# uC_radio.net
KiCad netlist of a schematic drawn in Altium Designer
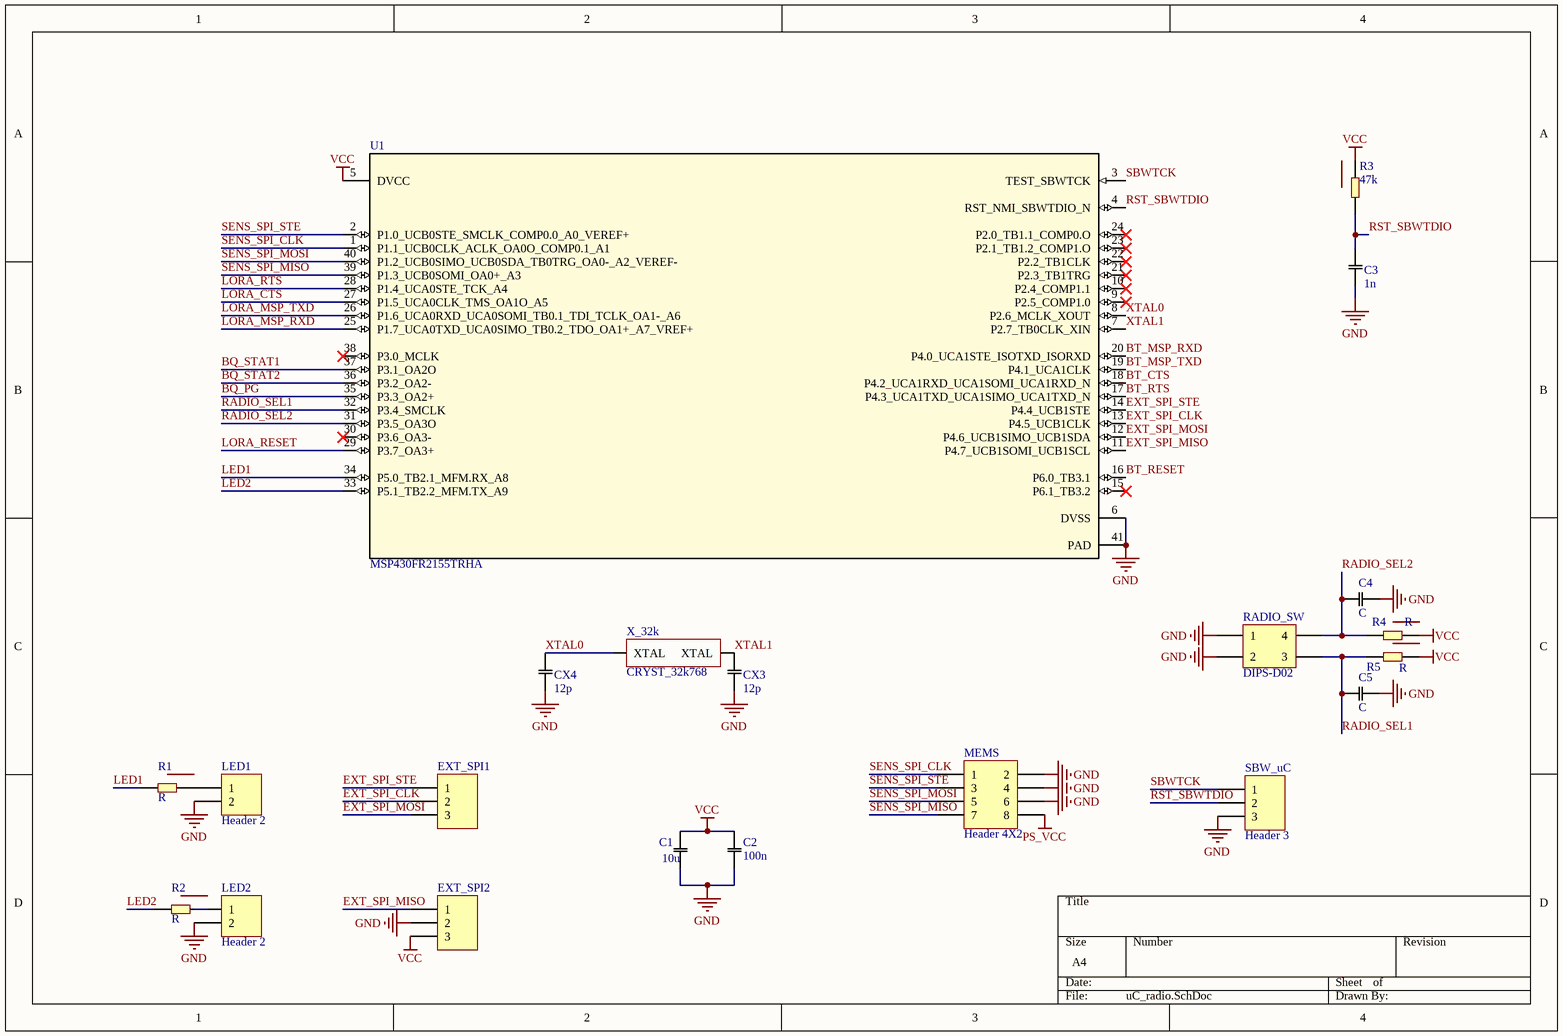
[diagram p0: uC_radio.SchDoc]

(export (version "E")
  (design (tool "Eeschema 10.0.6"))
  (components
    (comp (ref "C1")
      (value "10u")
      (footprint "402")
      (description "Capacitor")
      (libsource (lib "pass_comp") (part "C"))
    )
    (comp (ref "C2")
      (value "100n")
      (footprint "402")
      (description "Capacitor")
      (libsource (lib "pass_comp") (part "C"))
    )
    (comp (ref "C3")
      (value "1n")
      (footprint "402")
      (description "Capacitor")
      (libsource (lib "pass_comp") (part "C"))
    )
    (comp (ref "C4")
      (value "C")
      (footprint "603")
      (description "Capacitor")
      (libsource (lib "pass_comp") (part "C"))
    )
    (comp (ref "C5")
      (value "C")
      (footprint "603")
      (description "Capacitor")
      (libsource (lib "pass_comp") (part "C"))
    )
    (comp (ref "CX3")
      (value "12p")
      (footprint "402")
      (description "Capacitor")
      (libsource (lib "pass_comp") (part "C"))
    )
    (comp (ref "CX4")
      (value "12p")
      (footprint "402")
      (description "Capacitor")
      (libsource (lib "pass_comp") (part "C"))
    )
    (comp (ref "EXT_SPI1")
      (value "~")
      (footprint "HDR1X3")
      (description "Header, 3-Pin")
      (fields (field (name "PUBLISHER") "Altium Limited"))
      (libsource (lib "Miscellaneous Connectors") (part "Header 3"))
    )
    (comp (ref "EXT_SPI2")
      (value "~")
      (footprint "HDR1X3")
      (description "Header, 3-Pin")
      (fields (field (name "PUBLISHER") "Altium Limited"))
      (libsource (lib "Miscellaneous Connectors") (part "Header 3"))
    )
    (comp (ref "LED1")
      (value "Header 2")
      (footprint "HDR1X2")
      (description "Header, 2-Pin")
      (fields (field (name "PUBLISHER") "Altium Limited"))
      (libsource (lib "Miscellaneous Connectors") (part "Header 2"))
    )
    (comp (ref "LED2")
      (value "Header 2")
      (footprint "HDR1X2")
      (description "Header, 2-Pin")
      (fields (field (name "PUBLISHER") "Altium Limited"))
      (libsource (lib "Miscellaneous Connectors") (part "Header 2"))
    )
    (comp (ref "MEMS")
      (value "Header 4X2")
      (footprint "HDR2X4")
      (description "Header, 4-Pin, Dual row")
      (fields (field (name "PUBLISHER") "Altium Limited"))
      (libsource (lib "Miscellaneous Connectors") (part "Header 4X2"))
    )
    (comp (ref "R1") (value "R") (footprint "402") (description "Resistor") (libsource (lib "") (part "R_1")))
    (comp (ref "R2") (value "R") (footprint "402") (description "Resistor") (libsource (lib "") (part "R_1")))
    (comp (ref "R3")
      (value "47k")
      (footprint "402")
      (description "Resistor")
      (libsource (lib "pass_comp") (part "R"))
    )
    (comp (ref "R4") (value "R") (footprint "402") (description "Resistor") (libsource (lib "") (part "R_1")))
    (comp (ref "R5") (value "R") (footprint "402") (description "Resistor") (libsource (lib "") (part "R_1")))
    (comp (ref "RADIO_SW")
      (value "DIPS-D02")
      (footprint "DIPS-02")
      (libsource (lib "env_sens") (part "DIPS-D02"))
    )
    (comp (ref "SBW_uC")
      (value "Header 3")
      (footprint "HDR1X3")
      (description "Header, 3-Pin")
      (fields (field (name "PUBLISHER") "Altium Limited"))
      (libsource (lib "Miscellaneous Connectors") (part "Header 3"))
    )
    (comp (ref "U1")
      (value "MSP430FR2155TRHA")
      (footprint "RHA0040E_NV")
      (description "Imported")
      (fields
        (field (name "MANUFACTURER") "Texas Instruments")
        (field (name "PARTNUMBER") "MSP430FR2355TRHAR")
      )
      (libsource (lib "env_sens") (part "MSP430FR2155TRHA"))
    )
    (comp (ref "X_32k")
      (value "CRYST_32k768")
      (footprint "CRYST 32.768 kHz")
      (libsource (lib "env_sens") (part "CRYST_32k768"))
    )
  )
  (nets
    (net (code "1") (name "/BQ_PG") (class "Default")
      (node (ref "U1") (pin "35") (pinfunction "P3.3_OA2+_35") (pintype "bidirectional"))
    )
    (net (code "2") (name "/BQ_STAT1") (class "Default")
      (node (ref "U1") (pin "37") (pinfunction "P3.1_OA2O_37") (pintype "bidirectional"))
    )
    (net (code "3") (name "/BQ_STAT2") (class "Default")
      (node (ref "U1") (pin "36") (pinfunction "P3.2_OA2-_36") (pintype "bidirectional"))
    )
    (net (code "4") (name "/BT_CTS") (class "Default")
      (node (ref "U1") (pin "18") (pinfunction "P4.2_UCA1RXD_UCA1SOMI_UCA1RXD_N_18") (pintype "bidirectional"))
    )
    (net (code "5") (name "/BT_MSP_RXD") (class "Default")
      (node (ref "U1") (pin "20") (pinfunction "P4.0_UCA1STE_ISOTXD_ISORXD_20") (pintype "bidirectional"))
    )
    (net (code "6") (name "/BT_MSP_TXD") (class "Default")
      (node (ref "U1") (pin "19") (pinfunction "P4.1_UCA1CLK_19") (pintype "bidirectional"))
    )
    (net (code "7") (name "/BT_RESET") (class "Default")
      (node (ref "U1") (pin "16") (pinfunction "P6.0_TB3.1_16") (pintype "bidirectional"))
    )
    (net (code "8") (name "/BT_RTS") (class "Default")
      (node (ref "U1") (pin "17") (pinfunction "P4.3_UCA1TXD_UCA1SIMO_UCA1TXD_N_17") (pintype "bidirectional"))
    )
    (net (code "9") (name "/EXT_SPI_CLK") (class "Default")
      (node (ref "EXT_SPI1") (pin "2") (pinfunction "2_2") (pintype "passive"))
      (node (ref "U1") (pin "13") (pinfunction "P4.5_UCB1CLK_13") (pintype "bidirectional"))
    )
    (net (code "10") (name "/EXT_SPI_MISO") (class "Default")
      (node (ref "EXT_SPI2") (pin "1") (pinfunction "1_1") (pintype "passive"))
      (node (ref "U1") (pin "11") (pinfunction "P4.7_UCB1SOMI_UCB1SCL_11") (pintype "bidirectional"))
    )
    (net (code "11") (name "/EXT_SPI_MOSI") (class "Default")
      (node (ref "EXT_SPI1") (pin "3") (pinfunction "3_3") (pintype "passive"))
      (node (ref "U1") (pin "12") (pinfunction "P4.6_UCB1SIMO_UCB1SDA_12") (pintype "bidirectional"))
    )
    (net (code "12") (name "/EXT_SPI_STE") (class "Default")
      (node (ref "EXT_SPI1") (pin "1") (pinfunction "1_1") (pintype "passive"))
      (node (ref "U1") (pin "14") (pinfunction "P4.4_UCB1STE_14") (pintype "bidirectional"))
    )
    (net (code "13") (name "/LED1") (class "Default")
      (node (ref "R1") (pin "1") (pintype "passive"))
      (node (ref "U1") (pin "34") (pinfunction "P5.0_TB2.1_MFM.RX_A8_34") (pintype "bidirectional"))
    )
    (net (code "14") (name "/LED2") (class "Default")
      (node (ref "R2") (pin "1") (pintype "passive"))
      (node (ref "U1") (pin "33") (pinfunction "P5.1_TB2.2_MFM.TX_A9_33") (pintype "bidirectional"))
    )
    (net (code "15") (name "/LORA_CTS") (class "Default")
      (node (ref "U1") (pin "27") (pinfunction "P1.5_UCA0CLK_TMS_OA1O_A5_27") (pintype "bidirectional"))
    )
    (net (code "16") (name "/LORA_MSP_RXD") (class "Default")
      (node (ref "U1") (pin "25") (pinfunction "P1.7_UCA0TXD_UCA0SIMO_TB0.2_TDO_OA1+_A7_VREF+_25") (pintype "bidirectional"))
    )
    (net (code "17") (name "/LORA_MSP_TXD") (class "Default")
      (node (ref "U1") (pin "26") (pinfunction "P1.6_UCA0RXD_UCA0SOMI_TB0.1_TDI_TCLK_OA1-_A6_26") (pintype "bidirectional"))
    )
    (net (code "18") (name "/LORA_RESET") (class "Default")
      (node (ref "U1") (pin "29") (pinfunction "P3.7_OA3+_29") (pintype "bidirectional"))
    )
    (net (code "19") (name "/LORA_RTS") (class "Default")
      (node (ref "U1") (pin "28") (pinfunction "P1.4_UCA0STE_TCK_A4_28") (pintype "bidirectional"))
    )
    (net (code "20") (name "/RADIO_SEL1") (class "Default")
      (node (ref "C5") (pin "1") (pintype "passive"))
      (node (ref "R5") (pin "1") (pintype "passive"))
      (node (ref "RADIO_SW") (pin "3") (pinfunction "3_3") (pintype "passive"))
      (node (ref "U1") (pin "32") (pinfunction "P3.4_SMCLK_32") (pintype "bidirectional"))
    )
    (net (code "21") (name "/RADIO_SEL2") (class "Default")
      (node (ref "C4") (pin "1") (pintype "passive"))
      (node (ref "R4") (pin "1") (pintype "passive"))
      (node (ref "RADIO_SW") (pin "4") (pinfunction "4_4") (pintype "passive"))
      (node (ref "U1") (pin "31") (pinfunction "P3.5_OA3O_31") (pintype "bidirectional"))
    )
    (net (code "22") (name "/RST_SBWTDIO") (class "Default")
      (node (ref "C3") (pin "2") (pintype "passive"))
      (node (ref "R3") (pin "1") (pintype "passive"))
      (node (ref "SBW_uC") (pin "2") (pinfunction "2_2") (pintype "passive"))
      (node (ref "U1") (pin "4") (pinfunction "RST_NMI_SBWTDIO_N_4") (pintype "bidirectional"))
    )
    (net (code "23") (name "/SBWTCK") (class "Default")
      (node (ref "SBW_uC") (pin "1") (pinfunction "1_1") (pintype "passive"))
      (node (ref "U1") (pin "3") (pinfunction "TEST_SBWTCK_3") (pintype "input"))
    )
    (net (code "24") (name "/SENS_SPI_CLK") (class "Default")
      (node (ref "MEMS") (pin "1") (pinfunction "1_1") (pintype "passive"))
      (node (ref "U1") (pin "1") (pinfunction "P1.1_UCB0CLK_ACLK_OA0O_COMP0.1_A1_1") (pintype "bidirectional"))
    )
    (net (code "25") (name "/SENS_SPI_MISO") (class "Default")
      (node (ref "MEMS") (pin "7") (pinfunction "7_7") (pintype "passive"))
      (node (ref "U1") (pin "39") (pinfunction "P1.3_UCB0SOMI_OA0+_A3_39") (pintype "bidirectional"))
    )
    (net (code "26") (name "/SENS_SPI_MOSI") (class "Default")
      (node (ref "MEMS") (pin "5") (pinfunction "5_5") (pintype "passive"))
      (node (ref "U1") (pin "40") (pinfunction "P1.2_UCB0SIMO_UCB0SDA_TB0TRG_OA0-_A2_VEREF-_40") (pintype "bidirectional"))
    )
    (net (code "27") (name "/SENS_SPI_STE") (class "Default")
      (node (ref "MEMS") (pin "3") (pinfunction "3_3") (pintype "passive"))
      (node (ref "U1") (pin "2") (pinfunction "P1.0_UCB0STE_SMCLK_COMP0.0_A0_VEREF+_2") (pintype "bidirectional"))
    )
    (net (code "28") (name "/XTAL0") (class "Default")
      (node (ref "CX4") (pin "2") (pintype "passive"))
      (node (ref "U1") (pin "8") (pinfunction "P2.6_MCLK_XOUT_8") (pintype "bidirectional"))
      (node (ref "X_32k") (pin "2") (pinfunction "XTAL_2") (pintype "passive"))
    )
    (net (code "29") (name "/XTAL1") (class "Default")
      (node (ref "CX3") (pin "2") (pintype "passive"))
      (node (ref "U1") (pin "7") (pinfunction "P2.7_TB0CLK_XIN_7") (pintype "bidirectional"))
      (node (ref "X_32k") (pin "1") (pinfunction "XTAL_1") (pintype "passive"))
    )
    (net (code "30") (name "GND") (class "Default")
      (node (ref "C1") (pin "1") (pintype "passive"))
      (node (ref "C2") (pin "1") (pintype "passive"))
      (node (ref "C3") (pin "1") (pintype "passive"))
      (node (ref "C4") (pin "2") (pintype "passive"))
      (node (ref "C5") (pin "2") (pintype "passive"))
      (node (ref "CX3") (pin "1") (pintype "passive"))
      (node (ref "CX4") (pin "1") (pintype "passive"))
      (node (ref "EXT_SPI2") (pin "2") (pinfunction "2_2") (pintype "passive"))
      (node (ref "LED1") (pin "2") (pinfunction "2_2") (pintype "passive"))
      (node (ref "LED2") (pin "2") (pinfunction "2_2") (pintype "passive"))
      (node (ref "MEMS") (pin "2") (pinfunction "2_2") (pintype "passive"))
      (node (ref "MEMS") (pin "4") (pinfunction "4_4") (pintype "passive"))
      (node (ref "MEMS") (pin "6") (pinfunction "6_6") (pintype "passive"))
      (node (ref "RADIO_SW") (pin "1") (pinfunction "1_1") (pintype "passive"))
      (node (ref "RADIO_SW") (pin "2") (pinfunction "2_2") (pintype "passive"))
      (node (ref "SBW_uC") (pin "3") (pinfunction "3_3") (pintype "passive"))
      (node (ref "U1") (pin "41") (pinfunction "PAD_41") (pintype "passive"))
      (node (ref "U1") (pin "6") (pinfunction "DVSS_6") (pintype "power_in"))
    )
    (net (code "31") (name "Net-(LED1-Pad1)") (class "Default")
      (node (ref "LED1") (pin "1") (pinfunction "1_1") (pintype "passive"))
      (node (ref "R1") (pin "2") (pintype "passive"))
    )
    (net (code "32") (name "Net-(LED2-Pad1)") (class "Default")
      (node (ref "LED2") (pin "1") (pinfunction "1_1") (pintype "passive"))
      (node (ref "R2") (pin "2") (pintype "passive"))
    )
    (net (code "33") (name "PS_VCC") (class "Default")
      (node (ref "MEMS") (pin "8") (pinfunction "8_8") (pintype "passive"))
    )
    (net (code "34") (name "VCC") (class "Default")
      (node (ref "C1") (pin "2") (pintype "passive"))
      (node (ref "C2") (pin "2") (pintype "passive"))
      (node (ref "EXT_SPI2") (pin "3") (pinfunction "3_3") (pintype "passive"))
      (node (ref "R3") (pin "2") (pintype "passive"))
      (node (ref "R4") (pin "2") (pintype "passive"))
      (node (ref "R5") (pin "2") (pintype "passive"))
      (node (ref "U1") (pin "5") (pinfunction "DVCC_5") (pintype "power_in"))
    )
    (net (code "35") (name "unconnected-(U1-P2.0_TB1.1_COMP0.O-Pad24)") (class "Default")
      (node (ref "U1") (pin "24") (pinfunction "P2.0_TB1.1_COMP0.O_24") (pintype "bidirectional+no_connect"))
    )
    (net (code "36") (name "unconnected-(U1-P2.1_TB1.2_COMP1.O-Pad23)") (class "Default")
      (node (ref "U1") (pin "23") (pinfunction "P2.1_TB1.2_COMP1.O_23") (pintype "bidirectional+no_connect"))
    )
    (net (code "37") (name "unconnected-(U1-P2.2_TB1CLK-Pad22)") (class "Default")
      (node (ref "U1") (pin "22") (pinfunction "P2.2_TB1CLK_22") (pintype "bidirectional+no_connect"))
    )
    (net (code "38") (name "unconnected-(U1-P2.3_TB1TRG-Pad21)") (class "Default")
      (node (ref "U1") (pin "21") (pinfunction "P2.3_TB1TRG_21") (pintype "bidirectional+no_connect"))
    )
    (net (code "39") (name "unconnected-(U1-P2.4_COMP1.1-Pad10)") (class "Default")
      (node (ref "U1") (pin "10") (pinfunction "P2.4_COMP1.1_10") (pintype "bidirectional+no_connect"))
    )
    (net (code "40") (name "unconnected-(U1-P2.5_COMP1.0-Pad9)") (class "Default")
      (node (ref "U1") (pin "9") (pinfunction "P2.5_COMP1.0_9") (pintype "bidirectional+no_connect"))
    )
    (net (code "41") (name "unconnected-(U1-P3.0_MCLK-Pad38)") (class "Default")
      (node (ref "U1") (pin "38") (pinfunction "P3.0_MCLK_38") (pintype "bidirectional+no_connect"))
    )
    (net (code "42") (name "unconnected-(U1-P3.6_OA3--Pad30)") (class "Default")
      (node (ref "U1") (pin "30") (pinfunction "P3.6_OA3-_30") (pintype "bidirectional+no_connect"))
    )
    (net (code "43") (name "unconnected-(U1-P6.1_TB3.2-Pad15)") (class "Default")
      (node (ref "U1") (pin "15") (pinfunction "P6.1_TB3.2_15") (pintype "bidirectional+no_connect"))
    )
  )
)
